# DMDConnector.net
KiCad netlist of a schematic drawn in EAGLE
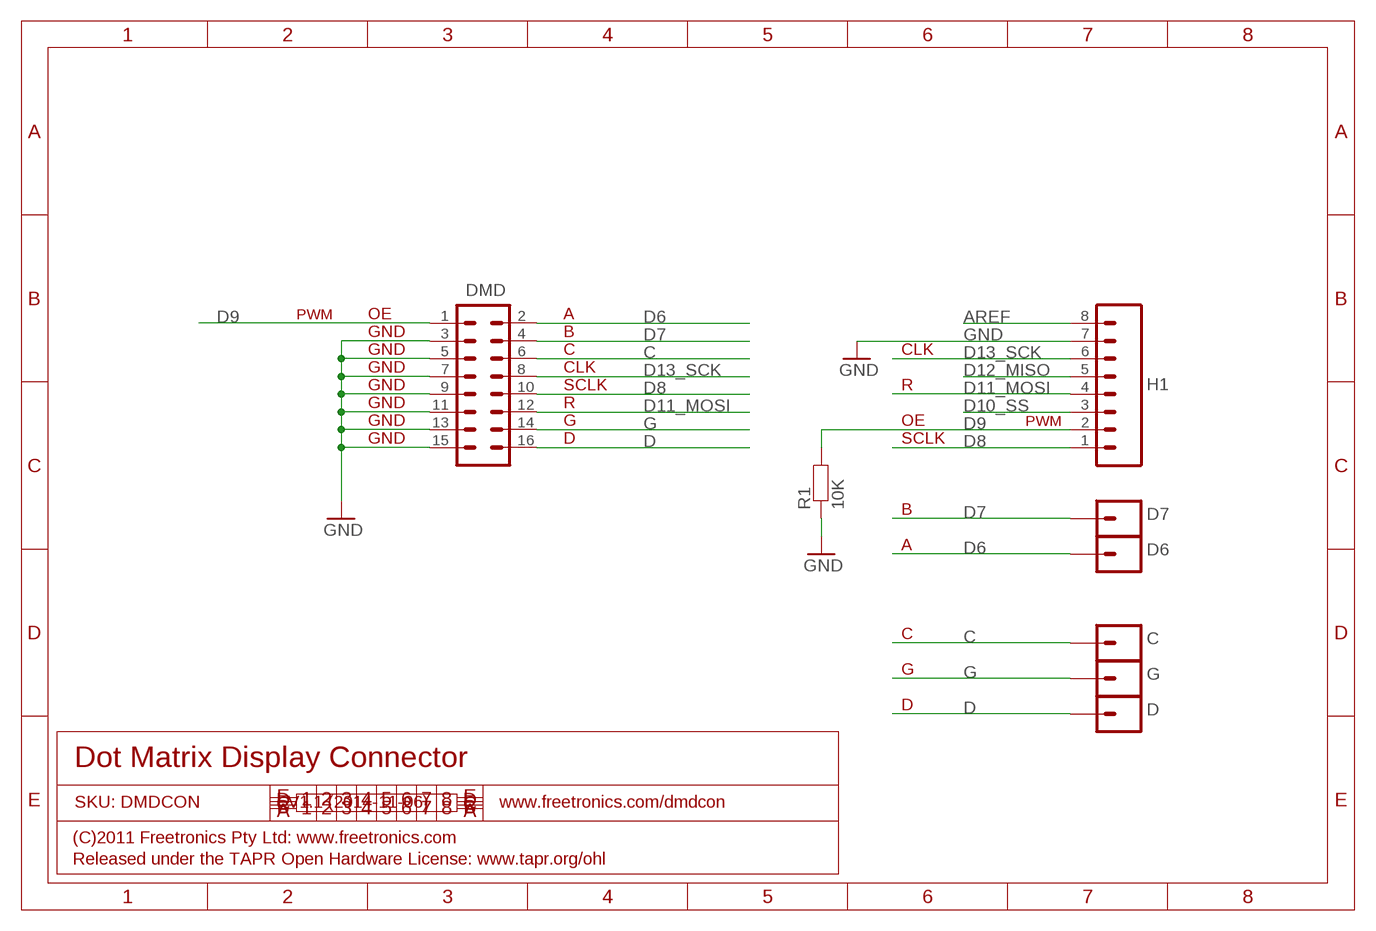
[diagram p0: schematic, sheet 1]

(export (version "E")
  (design (tool "Eeschema 10.0.6"))
  (components
    (comp (ref "C")
      (value "M01PTH")
      (footprint "eagle-import:1X01")
      (libsource (lib "eagle-import") (part "M01PTH"))
    )
    (comp (ref "D")
      (value "M01PTH")
      (footprint "eagle-import:1X01")
      (libsource (lib "eagle-import") (part "M01PTH"))
    )
    (comp (ref "D6")
      (value "M01PTH")
      (footprint "eagle-import:1X01")
      (libsource (lib "eagle-import") (part "M01PTH"))
    )
    (comp (ref "D7")
      (value "M01PTH")
      (footprint "eagle-import:1X01")
      (libsource (lib "eagle-import") (part "M01PTH"))
    )
    (comp (ref "DMD")
      (value "M08X2")
      (footprint "eagle-import:2X8-SMALLERPADS")
      (libsource (lib "eagle-import") (part "M08X2SMALLERPADS"))
    )
    (comp (ref "G")
      (value "M01PTH")
      (footprint "eagle-import:1X01")
      (libsource (lib "eagle-import") (part "M01PTH"))
    )
    (comp (ref "H1")
      (value "Digital_8_13")
      (footprint "eagle-import:1X08")
      (libsource (lib "eagle-import") (part "M08"))
    )
    (comp (ref "R1")
      (value "10K")
      (footprint "eagle-import:0805")
      (libsource (lib "eagle-import") (part "RESISTOR0805"))
    )
  )
  (nets
    (net (code "1") (name "/AREF") (class "Default")
      (node (ref "H1") (pin "8") (pinfunction "8_8") (pintype "passive"))
    )
    (net (code "2") (name "/C") (class "Default")
      (node (ref "C") (pin "1") (pinfunction "1_1") (pintype "passive"))
      (node (ref "DMD") (pin "6") (pinfunction "6_6") (pintype "passive"))
    )
    (net (code "3") (name "/D") (class "Default")
      (node (ref "D") (pin "1") (pinfunction "1_1") (pintype "passive"))
      (node (ref "DMD") (pin "16") (pinfunction "16_16") (pintype "passive"))
    )
    (net (code "4") (name "/D6") (class "Default")
      (node (ref "D6") (pin "1") (pinfunction "1_1") (pintype "passive"))
      (node (ref "DMD") (pin "2") (pinfunction "2_2") (pintype "passive"))
    )
    (net (code "5") (name "/D7") (class "Default")
      (node (ref "D7") (pin "1") (pinfunction "1_1") (pintype "passive"))
      (node (ref "DMD") (pin "4") (pinfunction "4_4") (pintype "passive"))
    )
    (net (code "6") (name "/D8") (class "Default")
      (node (ref "DMD") (pin "10") (pinfunction "10_10") (pintype "passive"))
      (node (ref "H1") (pin "1") (pinfunction "1_1") (pintype "passive"))
    )
    (net (code "7") (name "/D9") (class "Default")
      (node (ref "DMD") (pin "1") (pinfunction "1_1") (pintype "passive"))
      (node (ref "H1") (pin "2") (pinfunction "2_2") (pintype "passive"))
      (node (ref "R1") (pin "2") (pinfunction "2_2") (pintype "passive"))
    )
    (net (code "8") (name "/D10_SS") (class "Default")
      (node (ref "H1") (pin "3") (pinfunction "3_3") (pintype "passive"))
    )
    (net (code "9") (name "/D11_MOSI") (class "Default")
      (node (ref "DMD") (pin "12") (pinfunction "12_12") (pintype "passive"))
      (node (ref "H1") (pin "4") (pinfunction "4_4") (pintype "passive"))
    )
    (net (code "10") (name "/D12_MISO") (class "Default")
      (node (ref "H1") (pin "5") (pinfunction "5_5") (pintype "passive"))
    )
    (net (code "11") (name "/D13_SCK") (class "Default")
      (node (ref "DMD") (pin "8") (pinfunction "8_8") (pintype "passive"))
      (node (ref "H1") (pin "6") (pinfunction "6_6") (pintype "passive"))
    )
    (net (code "12") (name "/G") (class "Default")
      (node (ref "DMD") (pin "14") (pinfunction "14_14") (pintype "passive"))
      (node (ref "G") (pin "1") (pinfunction "1_1") (pintype "passive"))
    )
    (net (code "13") (name "GND") (class "Default")
      (node (ref "DMD") (pin "11") (pinfunction "11_11") (pintype "passive"))
      (node (ref "DMD") (pin "13") (pinfunction "13_13") (pintype "passive"))
      (node (ref "DMD") (pin "15") (pinfunction "15_15") (pintype "passive"))
      (node (ref "DMD") (pin "3") (pinfunction "3_3") (pintype "passive"))
      (node (ref "DMD") (pin "5") (pinfunction "5_5") (pintype "passive"))
      (node (ref "DMD") (pin "7") (pinfunction "7_7") (pintype "passive"))
      (node (ref "DMD") (pin "9") (pinfunction "9_9") (pintype "passive"))
      (node (ref "H1") (pin "7") (pinfunction "7_7") (pintype "passive"))
      (node (ref "R1") (pin "1") (pinfunction "1_1") (pintype "passive"))
    )
  )
)
